# audio_mux_stereo_eurorack.net
KiCad netlist of a schematic drawn in EAGLE
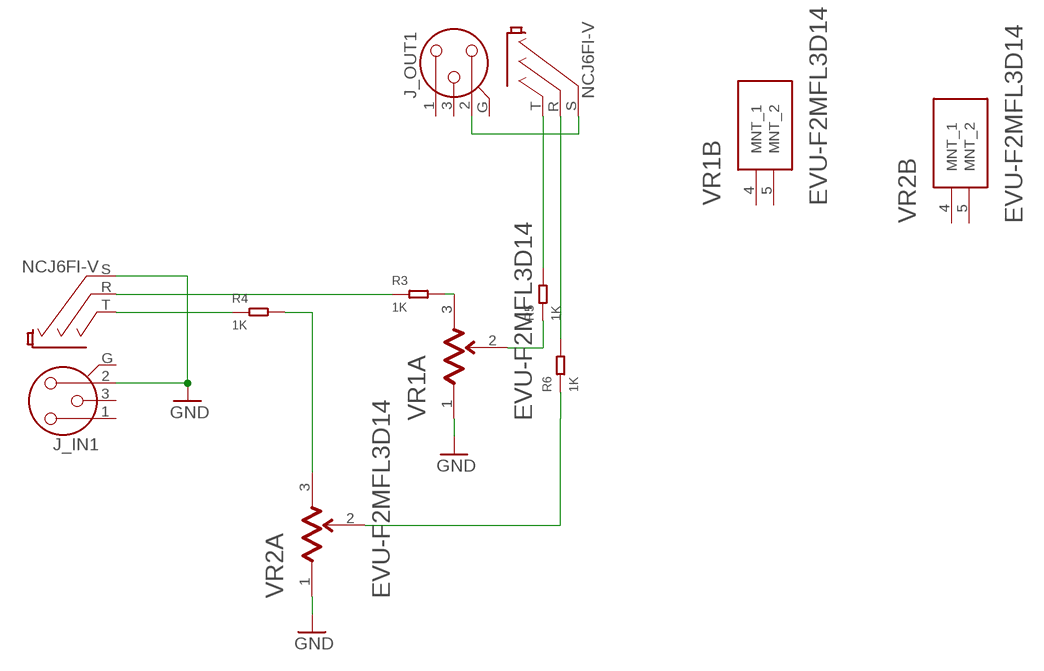
[diagram p0: schematic, sheet 1]

(export (version "E")
  (design (tool "Eeschema 10.0.6"))
  (components
    (comp (ref "J_IN1")
      (value "NCJ6FI-V")
      (footprint "eagle-import:NCJ6FI-V")
      (libsource (lib "eagle-import") (part "NCJ6FI-V"))
    )
    (comp (ref "J_OUT1")
      (value "NCJ6FI-V")
      (footprint "eagle-import:NCJ6FI-V")
      (libsource (lib "eagle-import") (part "NCJ6FI-V"))
    )
    (comp (ref "R3")
      (value "1K")
      (footprint "eagle-import:R0805")
      (fields (field (name "MPN") "RL0805JR-070R1L"))
      (libsource (lib "eagle-import") (part "SMD-RES-0.1R-5%-1/8W(0805)"))
    )
    (comp (ref "R4")
      (value "1K")
      (footprint "eagle-import:R0805")
      (fields (field (name "MPN") "RL0805JR-070R1L"))
      (libsource (lib "eagle-import") (part "SMD-RES-0.1R-5%-1/8W(0805)"))
    )
    (comp (ref "R5")
      (value "1K")
      (footprint "eagle-import:R0805")
      (fields (field (name "MPN") "RL0805JR-070R1L"))
      (libsource (lib "eagle-import") (part "SMD-RES-0.1R-5%-1/8W(0805)"))
    )
    (comp (ref "R6")
      (value "1K")
      (footprint "eagle-import:R0805")
      (fields (field (name "MPN") "RL0805JR-070R1L"))
      (libsource (lib "eagle-import") (part "SMD-RES-0.1R-5%-1/8W(0805)"))
    )
    (comp (ref "VR1")
      (value "PANASONIC_EVU-F2MFL3D14PANASONIC_EVU-F2MFL3D14_0_0")
      (footprint "eagle-import:PANASONIC_EVU-F2MFL3D14_0")
      (fields
        (field (name "DIGIKEY_PART_NUMBER") "P3H8103-ND")
        (field (name "MF") "Panasonic")
        (field (name "MOUSER_PART_NUMBER") "667-EVU-F2MFL3D14")
      )
      (libsource (lib "eagle-import") (part "PANASONIC_EVU-F2MFL3D14PANASONIC_EVU-F2MFL3D14_0_0"))
    )
    (comp (ref "VR2")
      (value "PANASONIC_EVU-F2MFL3D14PANASONIC_EVU-F2MFL3D14_0_0")
      (footprint "eagle-import:PANASONIC_EVU-F2MFL3D14_0")
      (fields
        (field (name "DIGIKEY_PART_NUMBER") "P3H8103-ND")
        (field (name "MF") "Panasonic")
        (field (name "MOUSER_PART_NUMBER") "667-EVU-F2MFL3D14")
      )
      (libsource (lib "eagle-import") (part "PANASONIC_EVU-F2MFL3D14PANASONIC_EVU-F2MFL3D14_0_0"))
    )
  )
  (nets
    (net (code "1") (name "GND") (class "Default")
      (node (ref "J_IN1") (pin "2") (pinfunction "2_2") (pintype "passive"))
      (node (ref "J_IN1") (pin "S") (pinfunction "S_S") (pintype "passive"))
      (node (ref "VR1") (pin "1") (pinfunction "1_1") (pintype "bidirectional"))
      (node (ref "VR2") (pin "1") (pinfunction "1_1") (pintype "bidirectional"))
    )
    (net (code "2") (name "Net-(J_IN1-PadR)") (class "Default")
      (node (ref "J_IN1") (pin "R") (pinfunction "R_R") (pintype "passive"))
      (node (ref "R3") (pin "1") (pinfunction "1_1") (pintype "passive"))
    )
    (net (code "3") (name "Net-(J_IN1-PadT)") (class "Default")
      (node (ref "J_IN1") (pin "T") (pinfunction "T_T") (pintype "passive"))
      (node (ref "R4") (pin "1") (pinfunction "1_1") (pintype "passive"))
    )
    (net (code "4") (name "Net-(J_OUT1-Pad2)") (class "Default")
      (node (ref "J_OUT1") (pin "2") (pinfunction "2_2") (pintype "passive"))
      (node (ref "J_OUT1") (pin "S") (pinfunction "S_S") (pintype "passive"))
    )
    (net (code "5") (name "Net-(J_OUT1-PadR)") (class "Default")
      (node (ref "J_OUT1") (pin "R") (pinfunction "R_R") (pintype "passive"))
      (node (ref "R6") (pin "2") (pinfunction "2_2") (pintype "passive"))
    )
    (net (code "6") (name "Net-(J_OUT1-PadT)") (class "Default")
      (node (ref "J_OUT1") (pin "T") (pinfunction "T_T") (pintype "passive"))
      (node (ref "R5") (pin "2") (pinfunction "2_2") (pintype "passive"))
    )
    (net (code "7") (name "Net-(R3-Pad2)") (class "Default")
      (node (ref "R3") (pin "2") (pinfunction "2_2") (pintype "passive"))
      (node (ref "VR1") (pin "3") (pinfunction "3_3") (pintype "bidirectional"))
    )
    (net (code "8") (name "Net-(R4-Pad2)") (class "Default")
      (node (ref "R4") (pin "2") (pinfunction "2_2") (pintype "passive"))
      (node (ref "VR2") (pin "3") (pinfunction "3_3") (pintype "bidirectional"))
    )
    (net (code "9") (name "Net-(R5-Pad1)") (class "Default")
      (node (ref "R5") (pin "1") (pinfunction "1_1") (pintype "passive"))
      (node (ref "VR1") (pin "2") (pinfunction "2_2") (pintype "bidirectional"))
    )
    (net (code "10") (name "Net-(R6-Pad1)") (class "Default")
      (node (ref "R6") (pin "1") (pinfunction "1_1") (pintype "passive"))
      (node (ref "VR2") (pin "2") (pinfunction "2_2") (pintype "bidirectional"))
    )
    (net (code "11") (name "unconnected-(J_IN1-Pad1)") (class "Default")
      (node (ref "J_IN1") (pin "1") (pinfunction "1_1") (pintype "passive"))
    )
    (net (code "12") (name "unconnected-(J_IN1-Pad3)") (class "Default")
      (node (ref "J_IN1") (pin "3") (pinfunction "3_3") (pintype "passive"))
    )
    (net (code "13") (name "unconnected-(J_IN1-PadG)") (class "Default")
      (node (ref "J_IN1") (pin "G") (pinfunction "G_G") (pintype "passive"))
    )
    (net (code "14") (name "unconnected-(J_OUT1-Pad1)") (class "Default")
      (node (ref "J_OUT1") (pin "1") (pinfunction "1_1") (pintype "passive"))
    )
    (net (code "15") (name "unconnected-(J_OUT1-Pad3)") (class "Default")
      (node (ref "J_OUT1") (pin "3") (pinfunction "3_3") (pintype "passive"))
    )
    (net (code "16") (name "unconnected-(J_OUT1-PadG)") (class "Default")
      (node (ref "J_OUT1") (pin "G") (pinfunction "G_G") (pintype "passive"))
    )
    (net (code "17") (name "unconnected-(VR1B-MNT_1-Pad4)") (class "Default")
      (node (ref "VR1") (pin "4") (pinfunction "MNT_1_4") (pintype "bidirectional"))
    )
    (net (code "18") (name "unconnected-(VR1B-MNT_2-Pad5)") (class "Default")
      (node (ref "VR1") (pin "5") (pinfunction "MNT_2_5") (pintype "bidirectional"))
    )
    (net (code "19") (name "unconnected-(VR2B-MNT_1-Pad4)") (class "Default")
      (node (ref "VR2") (pin "4") (pinfunction "MNT_1_4") (pintype "bidirectional"))
    )
    (net (code "20") (name "unconnected-(VR2B-MNT_2-Pad5)") (class "Default")
      (node (ref "VR2") (pin "5") (pinfunction "MNT_2_5") (pintype "bidirectional"))
    )
  )
)
